# JaidonHillBootcamp.net
KiCad netlist of a schematic drawn in Altium Designer
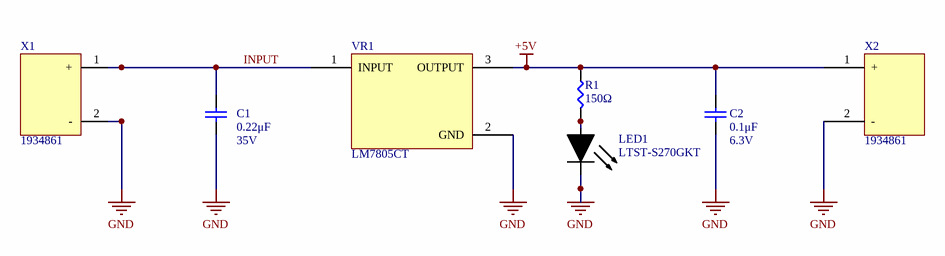
[diagram p0: JaidonHillBootcamp.SchDoc]

(export (version "E")
  (design (tool "Eeschema 10.0.6"))
  (components
    (comp (ref "C1")
      (value "0.22μF")
      (footprint "CAP0402")
      (description "CAP CER 0.22UF 35V X7R 0402")
      (fields (field (name "VOLTAGE RATING") "35V") (field (name "Comment") "CGA2B1X7R1V224K050BC"))
      (libsource (lib "Bootcamp_Schematic_Library") (part "CGA2B1X7R1V224K050BC"))
    )
    (comp (ref "C2")
      (value "0.1μF")
      (footprint "CAP0201")
      (description "CAP CER 0.1UF 6.3V X5R 0201")
      (fields (field (name "VOLTAGE RATING") "6.3V") (field (name "Comment") "CL03A104KQ3NNNC"))
      (libsource (lib "Bootcamp_Schematic_Library") (part "CL03A104KQ3NNNC"))
    )
    (comp (ref "LED1")
      (value "LTST-S270GKT")
      (footprint "LTST-S270GKT")
      (description "LED GREEN CLEAR SMD R/A")
      (libsource (lib "Bootcamp_Schematic_Library") (part "LTST-S270GKT"))
    )
    (comp (ref "R1")
      (value "150Ω")
      (footprint "RES0603")
      (description "RES 150 OHM 1% 1/10W 0603")
      (fields (field (name "Comment") "RC0603FR-07150RL"))
      (libsource (lib "Bootcamp_Schematic_Library") (part "RC0603FR-07150RL"))
    )
    (comp (ref "VR1")
      (value "LM7805CT")
      (footprint "TO-220-3")
      (description "Linear Voltage Regulators 1.5-A, 35-V, linear voltage regulator 3-TO-220 0 to 125")
      (libsource (lib "Bootcamp_Schematic_Library") (part "LM7805CT"))
    )
    (comp (ref "X1")
      (value "1934861")
      (footprint "1934861")
      (libsource (lib "Bootcamp_Schematic_Library") (part "1934861"))
    )
    (comp (ref "X2") (value "1934861") (footprint "1934861") (libsource (lib "") (part "1934861_1")))
  )
  (nets
    (net (code "1") (name "+5V") (class "Default")
      (node (ref "C2") (pin "2") (pinfunction "2_2") (pintype "passive"))
      (node (ref "R1") (pin "2") (pinfunction "2_2") (pintype "passive"))
      (node (ref "VR1") (pin "3") (pinfunction "OUTPUT_3") (pintype "passive"))
      (node (ref "X2") (pin "1") (pinfunction "+_1") (pintype "passive"))
    )
    (net (code "2") (name "/INPUT") (class "Default")
      (node (ref "C1") (pin "2") (pinfunction "2_2") (pintype "passive"))
      (node (ref "VR1") (pin "1") (pinfunction "INPUT_1") (pintype "passive"))
      (node (ref "X1") (pin "1") (pinfunction "+_1") (pintype "passive"))
    )
    (net (code "3") (name "GND") (class "Default")
      (node (ref "C1") (pin "1") (pinfunction "1_1") (pintype "passive"))
      (node (ref "C2") (pin "1") (pinfunction "1_1") (pintype "passive"))
      (node (ref "LED1") (pin "1") (pinfunction "1_1") (pintype "passive"))
      (node (ref "VR1") (pin "2") (pinfunction "GND_2") (pintype "passive"))
      (node (ref "X1") (pin "2") (pinfunction "-_2") (pintype "passive"))
      (node (ref "X2") (pin "2") (pinfunction "-_2") (pintype "passive"))
    )
    (net (code "4") (name "Net-(LED1-Pad2)") (class "Default")
      (node (ref "LED1") (pin "2") (pinfunction "2_2") (pintype "passive"))
      (node (ref "R1") (pin "1") (pinfunction "1_1") (pintype "passive"))
    )
  )
)
